# Mentor.net
KiCad netlist of a schematic drawn in EAGLE
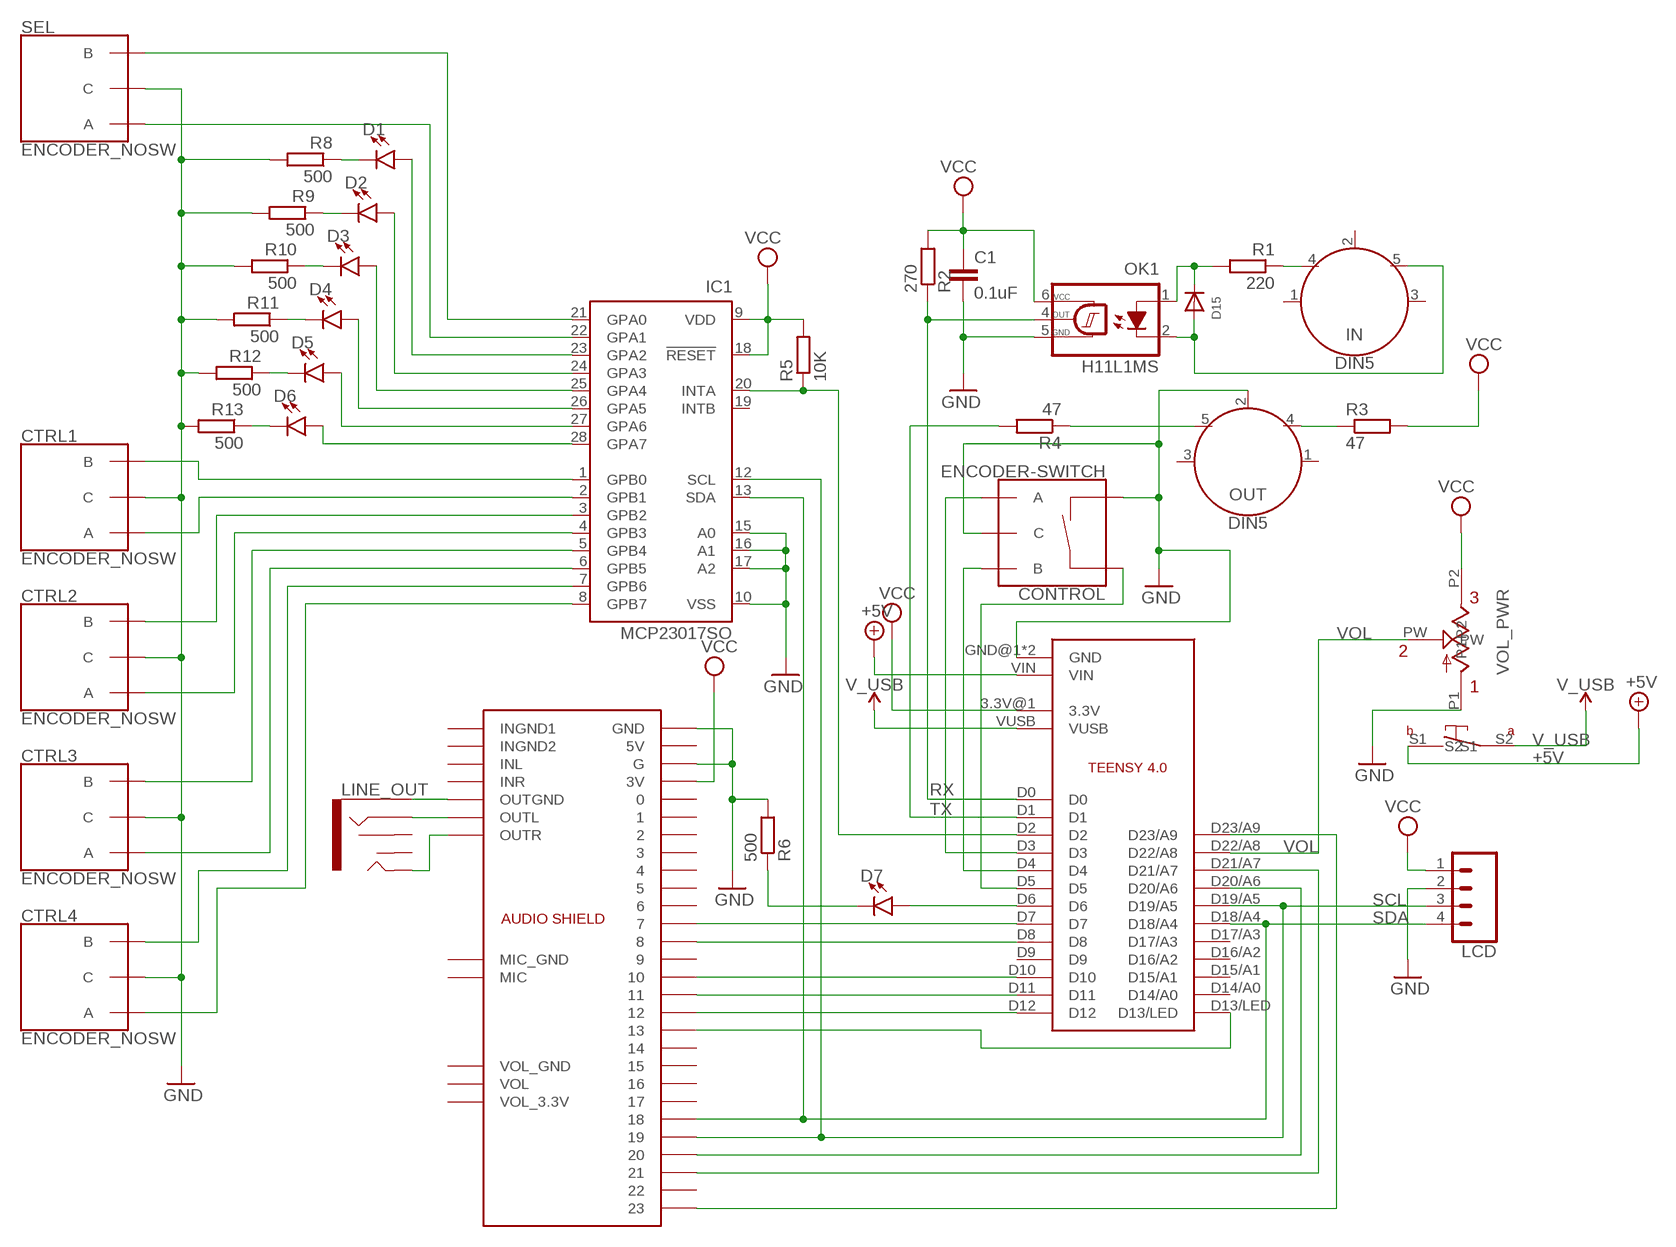
[diagram p0: schematic, sheet 1]

(export (version "E")
  (design (tool "Eeschema 10.0.6"))
  (components
    (comp (ref "C1")
      (value "0.1uF")
      (footprint "eagle-import:C0603K")
      (libsource (lib "eagle-import") (part "C-EUC0603K"))
    )
    (comp (ref "CONTROL")
      (value "ENCODER-SWITCH")
      (footprint "eagle-import:ROTARY_ENC_PLAIN")
      (libsource (lib "eagle-import") (part "ENCODER-SWITCH"))
    )
    (comp (ref "CTRL1")
      (value "ENCODER_NOSW")
      (footprint "eagle-import:ENCODER_NOSW")
      (libsource (lib "eagle-import") (part "ENCODER_NOSW"))
    )
    (comp (ref "CTRL2")
      (value "ENCODER_NOSW")
      (footprint "eagle-import:ENCODER_NOSW")
      (libsource (lib "eagle-import") (part "ENCODER_NOSW"))
    )
    (comp (ref "CTRL3")
      (value "ENCODER_NOSW")
      (footprint "eagle-import:ENCODER_NOSW")
      (libsource (lib "eagle-import") (part "ENCODER_NOSW"))
    )
    (comp (ref "CTRL4")
      (value "ENCODER_NOSW")
      (footprint "eagle-import:ENCODER_NOSW")
      (libsource (lib "eagle-import") (part "ENCODER_NOSW"))
    )
    (comp (ref "D1")
      (value "LED3MM")
      (footprint "eagle-import:LED_3MM")
      (fields (field (name "PROD_ID") "DIO-08794"))
      (libsource (lib "eagle-import") (part "LED3MM"))
    )
    (comp (ref "D2")
      (value "LED3MM")
      (footprint "eagle-import:LED_3MM")
      (fields (field (name "PROD_ID") "DIO-08794"))
      (libsource (lib "eagle-import") (part "LED3MM"))
    )
    (comp (ref "D3")
      (value "LED3MM")
      (footprint "eagle-import:LED_3MM")
      (fields (field (name "PROD_ID") "DIO-08794"))
      (libsource (lib "eagle-import") (part "LED3MM"))
    )
    (comp (ref "D4")
      (value "LED3MM")
      (footprint "eagle-import:LED_3MM")
      (fields (field (name "PROD_ID") "DIO-08794"))
      (libsource (lib "eagle-import") (part "LED3MM"))
    )
    (comp (ref "D5")
      (value "LED3MM")
      (footprint "eagle-import:LED_3MM")
      (fields (field (name "PROD_ID") "DIO-08794"))
      (libsource (lib "eagle-import") (part "LED3MM"))
    )
    (comp (ref "D6")
      (value "LED3MM")
      (footprint "eagle-import:LED_3MM")
      (fields (field (name "PROD_ID") "DIO-08794"))
      (libsource (lib "eagle-import") (part "LED3MM"))
    )
    (comp (ref "D7")
      (value "LED3MM")
      (footprint "eagle-import:LED_3MM")
      (fields (field (name "PROD_ID") "DIO-08794"))
      (libsource (lib "eagle-import") (part "LED3MM"))
    )
    (comp (ref "D15")
      (value "DIODESOD-123")
      (footprint "eagle-import:SOD-123")
      (libsource (lib "eagle-import") (part "DIODESOD-123"))
    )
    (comp (ref "IC1")
      (value "MCP23017SO")
      (footprint "eagle-import:SO28W")
      (libsource (lib "eagle-import") (part "MCP23017SO"))
    )
    (comp (ref "IN")
      (value "DIN5")
      (footprint "eagle-import:DIN5-RA-PTH")
      (libsource (lib "eagle-import") (part "DIN5"))
    )
    (comp (ref "LCD")
      (value "CONN_04LONGPADS")
      (footprint "eagle-import:1X04_LONGPADS")
      (libsource (lib "eagle-import") (part "CONN_04LONGPADS"))
    )
    (comp (ref "LINE_OUT")
      (value "AUDIO_JACK_3.5MM_PTH")
      (footprint "eagle-import:AUDIO-JACK")
      (libsource (lib "eagle-import") (part "AUDIO_JACK_3.5MM_PTH"))
    )
    (comp (ref "OK1")
      (value "H11L1MS")
      (footprint "eagle-import:DIL6-SMD")
      (libsource (lib "eagle-import") (part "H11LMS1"))
    )
    (comp (ref "OUT")
      (value "DIN5")
      (footprint "eagle-import:DIN5-RA-PTH")
      (libsource (lib "eagle-import") (part "DIN5"))
    )
    (comp (ref "R1")
      (value "220")
      (footprint "eagle-import:R0603")
      (libsource (lib "eagle-import") (part "R-EU_R0603"))
    )
    (comp (ref "R2")
      (value "270")
      (footprint "eagle-import:R0603")
      (libsource (lib "eagle-import") (part "R-EU_R0603"))
    )
    (comp (ref "R3")
      (value "47")
      (footprint "eagle-import:R0603")
      (libsource (lib "eagle-import") (part "R-EU_R0603"))
    )
    (comp (ref "R4")
      (value "47")
      (footprint "eagle-import:R0603")
      (libsource (lib "eagle-import") (part "R-EU_R0603"))
    )
    (comp (ref "R5")
      (value "10K")
      (footprint "eagle-import:R0603")
      (libsource (lib "eagle-import") (part "R-EU_R0603"))
    )
    (comp (ref "R6")
      (value "500")
      (footprint "eagle-import:R0603")
      (libsource (lib "eagle-import") (part "R-EU_R0603"))
    )
    (comp (ref "R8")
      (value "500")
      (footprint "eagle-import:R0603")
      (libsource (lib "eagle-import") (part "R-EU_R0603"))
    )
    (comp (ref "R9")
      (value "500")
      (footprint "eagle-import:R0603")
      (libsource (lib "eagle-import") (part "R-EU_R0603"))
    )
    (comp (ref "R10")
      (value "500")
      (footprint "eagle-import:R0603")
      (libsource (lib "eagle-import") (part "R-EU_R0603"))
    )
    (comp (ref "R11")
      (value "500")
      (footprint "eagle-import:R0603")
      (libsource (lib "eagle-import") (part "R-EU_R0603"))
    )
    (comp (ref "R12")
      (value "500")
      (footprint "eagle-import:R0603")
      (libsource (lib "eagle-import") (part "R-EU_R0603"))
    )
    (comp (ref "R13")
      (value "500")
      (footprint "eagle-import:R0603")
      (libsource (lib "eagle-import") (part "R-EU_R0603"))
    )
    (comp (ref "SEL")
      (value "ENCODER_NOSW")
      (footprint "eagle-import:ENCODER_NOSW")
      (libsource (lib "eagle-import") (part "ENCODER_NOSW"))
    )
    (comp (ref "U$2")
      (value "TEENSY4.0_SIMPLE")
      (footprint "eagle-import:TEENSY4.0_SIMPLE")
      (libsource (lib "eagle-import") (part "TEENSY4.0_SIMPLE"))
    )
    (comp (ref "U$3")
      (value "AUDIO SHIELD")
      (footprint "eagle-import:AUDIOSHIELD")
      (libsource (lib "eagle-import") (part "AUDIOSHIELD"))
    )
    (comp (ref "VOL_PWR")
      (value "10K")
      (footprint "eagle-import:RK097-SINGLE-W_SWITCH")
      (libsource (lib "eagle-import") (part "RK097-SINGLE-W/SWITCH-ROTARY"))
    )
  )
  (nets
    (net (code "1") (name "+5V") (class "Default")
      (node (ref "U$2") (pin "VIN") (pinfunction "VIN_VIN") (pintype "bidirectional"))
      (node (ref "VOL_PWR") (pin "S1") (pinfunction "S1_S1") (pintype "bidirectional"))
    )
    (net (code "2") (name "/RX") (class "Default")
      (node (ref "OK1") (pin "4") (pinfunction "OUT_4") (pintype "output"))
      (node (ref "R2") (pin "1") (pinfunction "1_1") (pintype "passive"))
      (node (ref "U$2") (pin "D0") (pinfunction "D0_D0") (pintype "bidirectional"))
    )
    (net (code "3") (name "/SCL") (class "Default")
      (node (ref "IC1") (pin "12") (pinfunction "SCL_12") (pintype "input"))
      (node (ref "LCD") (pin "3") (pinfunction "3_3") (pintype "passive"))
      (node (ref "U$2") (pin "D19/A5") (pinfunction "D19/A5_D19/A5") (pintype "bidirectional"))
      (node (ref "U$3") (pin "19") (pinfunction "19_19") (pintype "bidirectional"))
    )
    (net (code "4") (name "/SDA") (class "Default")
      (node (ref "IC1") (pin "13") (pinfunction "SDA_13") (pintype "bidirectional"))
      (node (ref "LCD") (pin "4") (pinfunction "4_4") (pintype "passive"))
      (node (ref "U$2") (pin "D18/A4") (pinfunction "D18/A4_D18/A4") (pintype "bidirectional"))
      (node (ref "U$3") (pin "18") (pinfunction "18_18") (pintype "bidirectional"))
    )
    (net (code "5") (name "/TX") (class "Default")
      (node (ref "R4") (pin "2") (pinfunction "2_2") (pintype "passive"))
      (node (ref "U$2") (pin "D1") (pinfunction "D1_D1") (pintype "bidirectional"))
    )
    (net (code "6") (name "/VOL") (class "Default")
      (node (ref "U$2") (pin "D22/A8") (pinfunction "D22/A8_D22/A8") (pintype "bidirectional"))
      (node (ref "VOL_PWR") (pin "PW") (pinfunction "PW_PW") (pintype "bidirectional"))
    )
    (net (code "7") (name "GND") (class "Default")
      (node (ref "C1") (pin "2") (pinfunction "2_2") (pintype "passive"))
      (node (ref "CONTROL") (pin "C") (pinfunction "C_C") (pintype "bidirectional"))
      (node (ref "CONTROL") (pin "SW-") (pinfunction "SW-_SW-") (pintype "bidirectional"))
      (node (ref "CTRL1") (pin "C") (pinfunction "C_C") (pintype "bidirectional"))
      (node (ref "CTRL2") (pin "C") (pinfunction "C_C") (pintype "bidirectional"))
      (node (ref "CTRL3") (pin "C") (pinfunction "C_C") (pintype "bidirectional"))
      (node (ref "CTRL4") (pin "C") (pinfunction "C_C") (pintype "bidirectional"))
      (node (ref "IC1") (pin "10") (pinfunction "VSS_10") (pintype "power_in"))
      (node (ref "IC1") (pin "15") (pinfunction "A0_15") (pintype "input"))
      (node (ref "IC1") (pin "16") (pinfunction "A1_16") (pintype "input"))
      (node (ref "IC1") (pin "17") (pinfunction "A2_17") (pintype "input"))
      (node (ref "LCD") (pin "2") (pinfunction "2_2") (pintype "passive"))
      (node (ref "OK1") (pin "5") (pinfunction "GND_5") (pintype "power_in"))
      (node (ref "OUT") (pin "2") (pinfunction "2_2") (pintype "bidirectional"))
      (node (ref "R10") (pin "2") (pinfunction "2_2") (pintype "passive"))
      (node (ref "R11") (pin "2") (pinfunction "2_2") (pintype "passive"))
      (node (ref "R12") (pin "2") (pinfunction "2_2") (pintype "passive"))
      (node (ref "R13") (pin "2") (pinfunction "2_2") (pintype "passive"))
      (node (ref "R6") (pin "2") (pinfunction "2_2") (pintype "passive"))
      (node (ref "R8") (pin "2") (pinfunction "2_2") (pintype "passive"))
      (node (ref "R9") (pin "2") (pinfunction "2_2") (pintype "passive"))
      (node (ref "SEL") (pin "C") (pinfunction "C_C") (pintype "bidirectional"))
      (node (ref "U$2") (pin "GND@1") (pinfunction "GND_GND@1") (pintype "bidirectional"))
      (node (ref "U$2") (pin "GND@2") (pinfunction "GND_GND@2") (pintype "bidirectional"))
      (node (ref "U$3") (pin "G") (pinfunction "G_G") (pintype "bidirectional"))
      (node (ref "U$3") (pin "GND") (pinfunction "GND_GND") (pintype "bidirectional"))
      (node (ref "VOL_PWR") (pin "P1") (pinfunction "P1_P1") (pintype "bidirectional"))
    )
    (net (code "8") (name "Net-(CONTROL-PadA)") (class "Default")
      (node (ref "CONTROL") (pin "A") (pinfunction "A_A") (pintype "bidirectional"))
      (node (ref "U$2") (pin "D3") (pinfunction "D3_D3") (pintype "bidirectional"))
    )
    (net (code "9") (name "Net-(CONTROL-PadB)") (class "Default")
      (node (ref "CONTROL") (pin "B") (pinfunction "B_B") (pintype "bidirectional"))
      (node (ref "U$2") (pin "D4") (pinfunction "D4_D4") (pintype "bidirectional"))
    )
    (net (code "10") (name "Net-(CONTROL-PadSW+)") (class "Default")
      (node (ref "CONTROL") (pin "SW+") (pinfunction "SW+_SW+") (pintype "bidirectional"))
      (node (ref "U$2") (pin "D5") (pinfunction "D5_D5") (pintype "bidirectional"))
    )
    (net (code "11") (name "Net-(D1-C)") (class "Default")
      (node (ref "D1") (pin "K") (pinfunction "C_K") (pintype "passive"))
      (node (ref "R8") (pin "1") (pinfunction "1_1") (pintype "passive"))
    )
    (net (code "12") (name "Net-(D2-C)") (class "Default")
      (node (ref "D2") (pin "K") (pinfunction "C_K") (pintype "passive"))
      (node (ref "R9") (pin "1") (pinfunction "1_1") (pintype "passive"))
    )
    (net (code "13") (name "Net-(D3-C)") (class "Default")
      (node (ref "D3") (pin "K") (pinfunction "C_K") (pintype "passive"))
      (node (ref "R10") (pin "1") (pinfunction "1_1") (pintype "passive"))
    )
    (net (code "14") (name "Net-(D4-C)") (class "Default")
      (node (ref "D4") (pin "K") (pinfunction "C_K") (pintype "passive"))
      (node (ref "R11") (pin "1") (pinfunction "1_1") (pintype "passive"))
    )
    (net (code "15") (name "Net-(D5-C)") (class "Default")
      (node (ref "D5") (pin "K") (pinfunction "C_K") (pintype "passive"))
      (node (ref "R12") (pin "1") (pinfunction "1_1") (pintype "passive"))
    )
    (net (code "16") (name "Net-(D6-C)") (class "Default")
      (node (ref "D6") (pin "K") (pinfunction "C_K") (pintype "passive"))
      (node (ref "R13") (pin "1") (pinfunction "1_1") (pintype "passive"))
    )
    (net (code "17") (name "Net-(D7-C)") (class "Default")
      (node (ref "D7") (pin "K") (pinfunction "C_K") (pintype "passive"))
      (node (ref "R6") (pin "1") (pinfunction "1_1") (pintype "passive"))
    )
    (net (code "18") (name "Net-(D7-PadA)") (class "Default")
      (node (ref "D7") (pin "A") (pinfunction "A_A") (pintype "passive"))
      (node (ref "U$2") (pin "D6") (pinfunction "D6_D6") (pintype "bidirectional"))
    )
    (net (code "19") (name "Net-(IC1-GPA0)") (class "Default")
      (node (ref "IC1") (pin "21") (pinfunction "GPA0_21") (pintype "bidirectional"))
      (node (ref "SEL") (pin "B") (pinfunction "B_B") (pintype "bidirectional"))
    )
    (net (code "20") (name "Net-(IC1-GPA1)") (class "Default")
      (node (ref "IC1") (pin "22") (pinfunction "GPA1_22") (pintype "bidirectional"))
      (node (ref "SEL") (pin "A") (pinfunction "A_A") (pintype "bidirectional"))
    )
    (net (code "21") (name "Net-(IC1-GPA2)") (class "Default")
      (node (ref "D1") (pin "A") (pinfunction "A_A") (pintype "passive"))
      (node (ref "IC1") (pin "23") (pinfunction "GPA2_23") (pintype "bidirectional"))
    )
    (net (code "22") (name "Net-(IC1-GPA3)") (class "Default")
      (node (ref "D2") (pin "A") (pinfunction "A_A") (pintype "passive"))
      (node (ref "IC1") (pin "24") (pinfunction "GPA3_24") (pintype "bidirectional"))
    )
    (net (code "23") (name "Net-(IC1-GPA4)") (class "Default")
      (node (ref "D3") (pin "A") (pinfunction "A_A") (pintype "passive"))
      (node (ref "IC1") (pin "25") (pinfunction "GPA4_25") (pintype "bidirectional"))
    )
    (net (code "24") (name "Net-(IC1-GPA5)") (class "Default")
      (node (ref "D4") (pin "A") (pinfunction "A_A") (pintype "passive"))
      (node (ref "IC1") (pin "26") (pinfunction "GPA5_26") (pintype "bidirectional"))
    )
    (net (code "25") (name "Net-(IC1-GPA6)") (class "Default")
      (node (ref "D5") (pin "A") (pinfunction "A_A") (pintype "passive"))
      (node (ref "IC1") (pin "27") (pinfunction "GPA6_27") (pintype "bidirectional"))
    )
    (net (code "26") (name "Net-(IC1-GPA7)") (class "Default")
      (node (ref "D6") (pin "A") (pinfunction "A_A") (pintype "passive"))
      (node (ref "IC1") (pin "28") (pinfunction "GPA7_28") (pintype "bidirectional"))
    )
    (net (code "27") (name "Net-(IC1-GPB0)") (class "Default")
      (node (ref "CTRL1") (pin "B") (pinfunction "B_B") (pintype "bidirectional"))
      (node (ref "IC1") (pin "1") (pinfunction "GPB0_1") (pintype "bidirectional"))
    )
    (net (code "28") (name "Net-(IC1-GPB1)") (class "Default")
      (node (ref "CTRL1") (pin "A") (pinfunction "A_A") (pintype "bidirectional"))
      (node (ref "IC1") (pin "2") (pinfunction "GPB1_2") (pintype "bidirectional"))
    )
    (net (code "29") (name "Net-(IC1-GPB2)") (class "Default")
      (node (ref "CTRL2") (pin "B") (pinfunction "B_B") (pintype "bidirectional"))
      (node (ref "IC1") (pin "3") (pinfunction "GPB2_3") (pintype "bidirectional"))
    )
    (net (code "30") (name "Net-(IC1-GPB3)") (class "Default")
      (node (ref "CTRL2") (pin "A") (pinfunction "A_A") (pintype "bidirectional"))
      (node (ref "IC1") (pin "4") (pinfunction "GPB3_4") (pintype "bidirectional"))
    )
    (net (code "31") (name "Net-(IC1-GPB4)") (class "Default")
      (node (ref "CTRL3") (pin "B") (pinfunction "B_B") (pintype "bidirectional"))
      (node (ref "IC1") (pin "5") (pinfunction "GPB4_5") (pintype "bidirectional"))
    )
    (net (code "32") (name "Net-(IC1-GPB5)") (class "Default")
      (node (ref "CTRL3") (pin "A") (pinfunction "A_A") (pintype "bidirectional"))
      (node (ref "IC1") (pin "6") (pinfunction "GPB5_6") (pintype "bidirectional"))
    )
    (net (code "33") (name "Net-(IC1-GPB6)") (class "Default")
      (node (ref "CTRL4") (pin "B") (pinfunction "B_B") (pintype "bidirectional"))
      (node (ref "IC1") (pin "7") (pinfunction "GPB6_7") (pintype "bidirectional"))
    )
    (net (code "34") (name "Net-(IC1-GPB7)") (class "Default")
      (node (ref "CTRL4") (pin "A") (pinfunction "A_A") (pintype "bidirectional"))
      (node (ref "IC1") (pin "8") (pinfunction "GPB7_8") (pintype "bidirectional"))
    )
    (net (code "35") (name "Net-(IC1-INTA)") (class "Default")
      (node (ref "IC1") (pin "20") (pinfunction "INTA_20") (pintype "output"))
      (node (ref "R5") (pin "1") (pinfunction "1_1") (pintype "passive"))
      (node (ref "U$2") (pin "D2") (pinfunction "D2_D2") (pintype "bidirectional"))
    )
    (net (code "36") (name "Net-(IN-Pad4)") (class "Default")
      (node (ref "IN") (pin "4") (pinfunction "4_4") (pintype "bidirectional"))
      (node (ref "R1") (pin "1") (pinfunction "1_1") (pintype "passive"))
    )
    (net (code "37") (name "Net-(LINE_OUT-PadRING)") (class "Default")
      (node (ref "LINE_OUT") (pin "RING") (pinfunction "RING_RING") (pintype "bidirectional"))
      (node (ref "U$3") (pin "OUTL") (pinfunction "OUTL_OUTL") (pintype "output"))
    )
    (net (code "38") (name "Net-(LINE_OUT-PadSLEEVE)") (class "Default")
      (node (ref "LINE_OUT") (pin "SLEEVE") (pinfunction "SLEEVE_SLEEVE") (pintype "bidirectional"))
      (node (ref "U$3") (pin "OUTGND") (pinfunction "OUTGND_OUTGND") (pintype "bidirectional"))
    )
    (net (code "39") (name "Net-(LINE_OUT-PadTIP)") (class "Default")
      (node (ref "LINE_OUT") (pin "TIP") (pinfunction "TIP_TIP") (pintype "bidirectional"))
      (node (ref "U$3") (pin "OUTR") (pinfunction "OUTR_OUTR") (pintype "output"))
    )
    (net (code "40") (name "Net-(OK1-A)") (class "Default")
      (node (ref "D15") (pin "C") (pinfunction "C_C") (pintype "passive"))
      (node (ref "OK1") (pin "1") (pinfunction "A_1") (pintype "passive"))
      (node (ref "R1") (pin "2") (pinfunction "2_2") (pintype "passive"))
    )
    (net (code "41") (name "Net-(OK1-C)") (class "Default")
      (node (ref "D15") (pin "A") (pinfunction "A_A") (pintype "passive"))
      (node (ref "IN") (pin "5") (pinfunction "5_5") (pintype "bidirectional"))
      (node (ref "OK1") (pin "2") (pinfunction "C_2") (pintype "passive"))
    )
    (net (code "42") (name "Net-(OUT-Pad4)") (class "Default")
      (node (ref "OUT") (pin "4") (pinfunction "4_4") (pintype "bidirectional"))
      (node (ref "R3") (pin "1") (pinfunction "1_1") (pintype "passive"))
    )
    (net (code "43") (name "Net-(OUT-Pad5)") (class "Default")
      (node (ref "OUT") (pin "5") (pinfunction "5_5") (pintype "bidirectional"))
      (node (ref "R4") (pin "1") (pinfunction "1_1") (pintype "passive"))
    )
    (net (code "44") (name "Net-(U$2-PadD7)") (class "Default")
      (node (ref "U$2") (pin "D7") (pinfunction "D7_D7") (pintype "bidirectional"))
      (node (ref "U$3") (pin "7") (pinfunction "7_7") (pintype "bidirectional"))
    )
    (net (code "45") (name "Net-(U$2-PadD8)") (class "Default")
      (node (ref "U$2") (pin "D8") (pinfunction "D8_D8") (pintype "bidirectional"))
      (node (ref "U$3") (pin "8") (pinfunction "8_8") (pintype "bidirectional"))
    )
    (net (code "46") (name "Net-(U$2-PadD10)") (class "Default")
      (node (ref "U$2") (pin "D10") (pinfunction "D10_D10") (pintype "bidirectional"))
      (node (ref "U$3") (pin "10") (pinfunction "10_10") (pintype "bidirectional"))
    )
    (net (code "47") (name "Net-(U$2-PadD11)") (class "Default")
      (node (ref "U$2") (pin "D11") (pinfunction "D11_D11") (pintype "bidirectional"))
      (node (ref "U$3") (pin "11") (pinfunction "11_11") (pintype "bidirectional"))
    )
    (net (code "48") (name "Net-(U$2-PadD12)") (class "Default")
      (node (ref "U$2") (pin "D12") (pinfunction "D12_D12") (pintype "bidirectional"))
      (node (ref "U$3") (pin "12") (pinfunction "12_12") (pintype "bidirectional"))
    )
    (net (code "49") (name "Net-(U$2-PadD13{slash}LED)") (class "Default")
      (node (ref "U$2") (pin "D13/LED") (pinfunction "D13/LED_D13/LED") (pintype "bidirectional"))
      (node (ref "U$3") (pin "13") (pinfunction "13_13") (pintype "bidirectional"))
    )
    (net (code "50") (name "Net-(U$2-PadD20{slash}A6)") (class "Default")
      (node (ref "U$2") (pin "D20/A6") (pinfunction "D20/A6_D20/A6") (pintype "bidirectional"))
      (node (ref "U$3") (pin "20") (pinfunction "20_20") (pintype "bidirectional"))
    )
    (net (code "51") (name "Net-(U$2-PadD21{slash}A7)") (class "Default")
      (node (ref "U$2") (pin "D21/A7") (pinfunction "D21/A7_D21/A7") (pintype "bidirectional"))
      (node (ref "U$3") (pin "21") (pinfunction "21_21") (pintype "bidirectional"))
    )
    (net (code "52") (name "Net-(U$2-PadD23{slash}A9)") (class "Default")
      (node (ref "U$2") (pin "D23/A9") (pinfunction "D23/A9_D23/A9") (pintype "bidirectional"))
      (node (ref "U$3") (pin "23") (pinfunction "23_23") (pintype "bidirectional"))
    )
    (net (code "53") (name "VCC") (class "Default")
      (node (ref "C1") (pin "1") (pinfunction "1_1") (pintype "passive"))
      (node (ref "IC1") (pin "18") (pinfunction "~{RESET}_18") (pintype "input"))
      (node (ref "IC1") (pin "9") (pinfunction "VDD_9") (pintype "power_in"))
      (node (ref "LCD") (pin "1") (pinfunction "1_1") (pintype "passive"))
      (node (ref "OK1") (pin "6") (pinfunction "VCC_6") (pintype "power_in"))
      (node (ref "R2") (pin "2") (pinfunction "2_2") (pintype "passive"))
      (node (ref "R3") (pin "2") (pinfunction "2_2") (pintype "passive"))
      (node (ref "R5") (pin "2") (pinfunction "2_2") (pintype "passive"))
      (node (ref "U$2") (pin "3.3V@1") (pinfunction "3.3V_3.3V@1") (pintype "bidirectional"))
      (node (ref "U$3") (pin "3V") (pinfunction "3V_3V") (pintype "bidirectional"))
      (node (ref "VOL_PWR") (pin "P2") (pinfunction "P2_P2") (pintype "bidirectional"))
    )
    (net (code "54") (name "V_USB") (class "Default")
      (node (ref "U$2") (pin "VUSB") (pinfunction "VUSB_VUSB") (pintype "bidirectional"))
      (node (ref "VOL_PWR") (pin "S2") (pinfunction "S2_S2") (pintype "bidirectional"))
    )
    (net (code "55") (name "unconnected-(IC1-INTB-Pad19)") (class "Default")
      (node (ref "IC1") (pin "19") (pinfunction "INTB_19") (pintype "output"))
    )
    (net (code "56") (name "unconnected-(IN-Pad1)") (class "Default")
      (node (ref "IN") (pin "1") (pinfunction "1_1") (pintype "bidirectional"))
    )
    (net (code "57") (name "unconnected-(IN-Pad2)") (class "Default")
      (node (ref "IN") (pin "2") (pinfunction "2_2") (pintype "bidirectional"))
    )
    (net (code "58") (name "unconnected-(IN-Pad3)") (class "Default")
      (node (ref "IN") (pin "3") (pinfunction "3_3") (pintype "bidirectional"))
    )
    (net (code "59") (name "unconnected-(LINE_OUT-PadRSH)") (class "Default")
      (node (ref "LINE_OUT") (pin "RSH") (pinfunction "RSH_RSH") (pintype "bidirectional"))
    )
    (net (code "60") (name "unconnected-(LINE_OUT-PadTSH)") (class "Default")
      (node (ref "LINE_OUT") (pin "TSH") (pinfunction "TSH_TSH") (pintype "bidirectional"))
    )
    (net (code "61") (name "unconnected-(OUT-Pad1)") (class "Default")
      (node (ref "OUT") (pin "1") (pinfunction "1_1") (pintype "bidirectional"))
    )
    (net (code "62") (name "unconnected-(OUT-Pad3)") (class "Default")
      (node (ref "OUT") (pin "3") (pinfunction "3_3") (pintype "bidirectional"))
    )
    (net (code "63") (name "unconnected-(U$2-PadD9)") (class "Default")
      (node (ref "U$2") (pin "D9") (pinfunction "D9_D9") (pintype "bidirectional"))
    )
    (net (code "64") (name "unconnected-(U$2-PadD14{slash}A0)") (class "Default")
      (node (ref "U$2") (pin "D14/A0") (pinfunction "D14/A0_D14/A0") (pintype "bidirectional"))
    )
    (net (code "65") (name "unconnected-(U$2-PadD15{slash}A1)") (class "Default")
      (node (ref "U$2") (pin "D15/A1") (pinfunction "D15/A1_D15/A1") (pintype "bidirectional"))
    )
    (net (code "66") (name "unconnected-(U$2-PadD16{slash}A2)") (class "Default")
      (node (ref "U$2") (pin "D16/A2") (pinfunction "D16/A2_D16/A2") (pintype "bidirectional"))
    )
    (net (code "67") (name "unconnected-(U$2-PadD17{slash}A3)") (class "Default")
      (node (ref "U$2") (pin "D17/A3") (pinfunction "D17/A3_D17/A3") (pintype "bidirectional"))
    )
    (net (code "68") (name "unconnected-(U$3-MIC_GND-PadGND_MIC)") (class "Default")
      (node (ref "U$3") (pin "GND_MIC") (pinfunction "MIC_GND_GND_MIC") (pintype "bidirectional"))
    )
    (net (code "69") (name "unconnected-(U$3-Pad0)") (class "Default")
      (node (ref "U$3") (pin "0") (pinfunction "0_0") (pintype "bidirectional"))
    )
    (net (code "70") (name "unconnected-(U$3-Pad1)") (class "Default")
      (node (ref "U$3") (pin "1") (pinfunction "1_1") (pintype "bidirectional"))
    )
    (net (code "71") (name "unconnected-(U$3-Pad2)") (class "Default")
      (node (ref "U$3") (pin "2") (pinfunction "2_2") (pintype "bidirectional"))
    )
    (net (code "72") (name "unconnected-(U$3-Pad3)") (class "Default")
      (node (ref "U$3") (pin "3") (pinfunction "3_3") (pintype "bidirectional"))
    )
    (net (code "73") (name "unconnected-(U$3-Pad4)") (class "Default")
      (node (ref "U$3") (pin "4") (pinfunction "4_4") (pintype "bidirectional"))
    )
    (net (code "74") (name "unconnected-(U$3-Pad5)") (class "Default")
      (node (ref "U$3") (pin "5") (pinfunction "5_5") (pintype "bidirectional"))
    )
    (net (code "75") (name "unconnected-(U$3-Pad5V)") (class "Default")
      (node (ref "U$3") (pin "5V") (pinfunction "5V_5V") (pintype "bidirectional"))
    )
    (net (code "76") (name "unconnected-(U$3-Pad6)") (class "Default")
      (node (ref "U$3") (pin "6") (pinfunction "6_6") (pintype "bidirectional"))
    )
    (net (code "77") (name "unconnected-(U$3-Pad9)") (class "Default")
      (node (ref "U$3") (pin "9") (pinfunction "9_9") (pintype "bidirectional"))
    )
    (net (code "78") (name "unconnected-(U$3-Pad14)") (class "Default")
      (node (ref "U$3") (pin "14") (pinfunction "14_14") (pintype "bidirectional"))
    )
    (net (code "79") (name "unconnected-(U$3-Pad15)") (class "Default")
      (node (ref "U$3") (pin "15") (pinfunction "15_15") (pintype "bidirectional"))
    )
    (net (code "80") (name "unconnected-(U$3-Pad16)") (class "Default")
      (node (ref "U$3") (pin "16") (pinfunction "16_16") (pintype "bidirectional"))
    )
    (net (code "81") (name "unconnected-(U$3-Pad17)") (class "Default")
      (node (ref "U$3") (pin "17") (pinfunction "17_17") (pintype "bidirectional"))
    )
    (net (code "82") (name "unconnected-(U$3-Pad22)") (class "Default")
      (node (ref "U$3") (pin "22") (pinfunction "22_22") (pintype "bidirectional"))
    )
    (net (code "83") (name "unconnected-(U$3-PadINGND1)") (class "Default")
      (node (ref "U$3") (pin "INGND1") (pinfunction "INGND1_INGND1") (pintype "bidirectional"))
    )
    (net (code "84") (name "unconnected-(U$3-PadINGND2)") (class "Default")
      (node (ref "U$3") (pin "INGND2") (pinfunction "INGND2_INGND2") (pintype "bidirectional"))
    )
    (net (code "85") (name "unconnected-(U$3-PadINL)") (class "Default")
      (node (ref "U$3") (pin "INL") (pinfunction "INL_INL") (pintype "input"))
    )
    (net (code "86") (name "unconnected-(U$3-PadINR)") (class "Default")
      (node (ref "U$3") (pin "INR") (pinfunction "INR_INR") (pintype "input"))
    )
    (net (code "87") (name "unconnected-(U$3-PadMIC)") (class "Default")
      (node (ref "U$3") (pin "MIC") (pinfunction "MIC_MIC") (pintype "input"))
    )
    (net (code "88") (name "unconnected-(U$3-PadVOL)") (class "Default")
      (node (ref "U$3") (pin "VOL") (pinfunction "VOL_VOL") (pintype "input"))
    )
    (net (code "89") (name "unconnected-(U$3-PadVOL_3.3V)") (class "Default")
      (node (ref "U$3") (pin "VOL_3.3V") (pinfunction "VOL_3.3V_VOL_3.3V") (pintype "bidirectional"))
    )
    (net (code "90") (name "unconnected-(U$3-PadVOL_GND)") (class "Default")
      (node (ref "U$3") (pin "VOL_GND") (pinfunction "VOL_GND_VOL_GND") (pintype "bidirectional"))
    )
  )
)
